# SBC-Accelerometer-v10.net
KiCad netlist of a schematic drawn in EAGLE
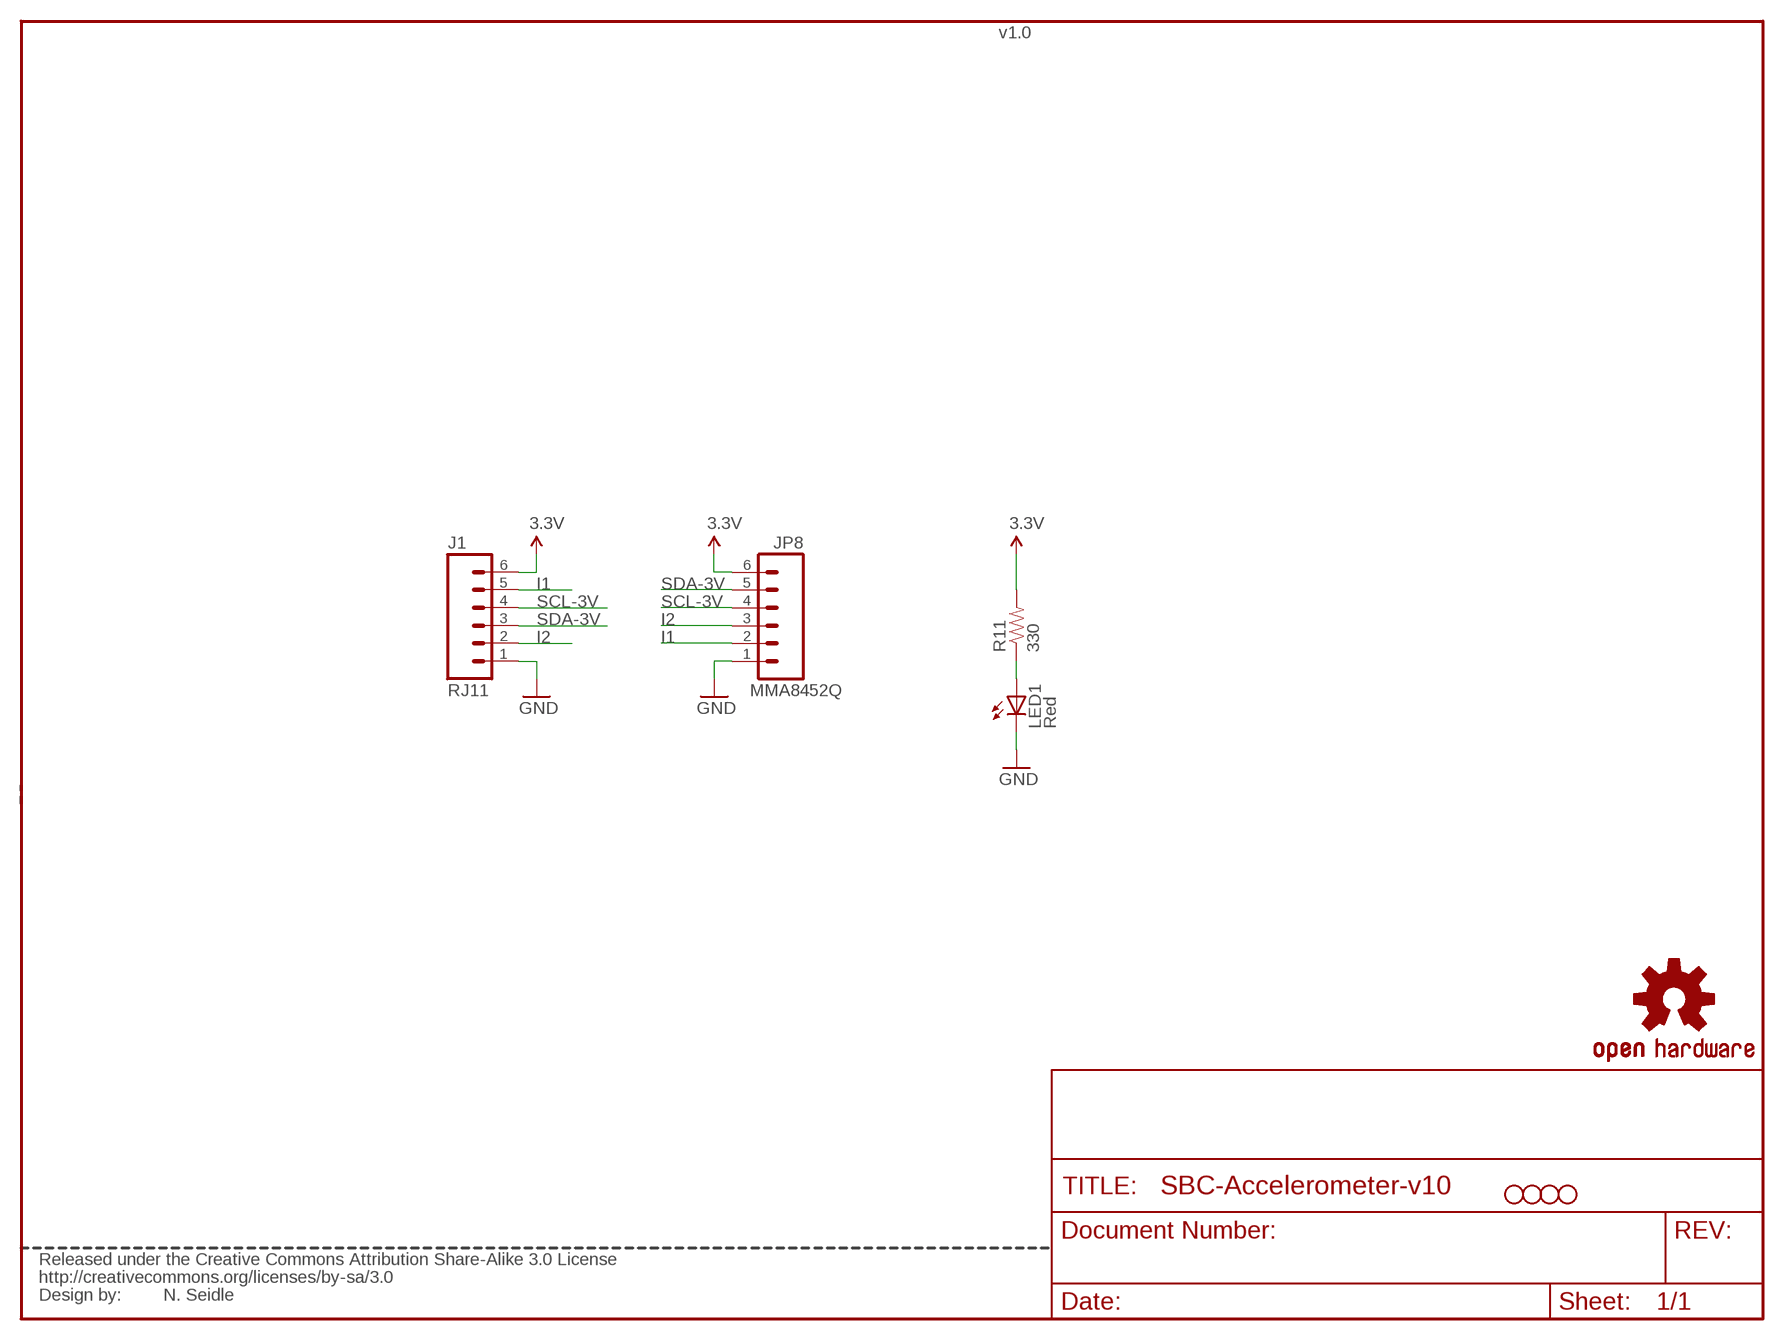
[diagram p0: schematic, sheet 1]

(export (version "E")
  (design (tool "Eeschema 10.0.6"))
  (components
    (comp (ref "J1")
      (value "RJ11")
      (footprint "eagle-import:RJ11-6")
      (libsource (lib "eagle-import") (part "RJ11-6PTH"))
    )
    (comp (ref "JP3")
      (value "STAND-OFF")
      (footprint "eagle-import:STAND-OFF")
      (libsource (lib "eagle-import") (part "STAND-OFF"))
    )
    (comp (ref "JP4")
      (value "STAND-OFF")
      (footprint "eagle-import:STAND-OFF")
      (libsource (lib "eagle-import") (part "STAND-OFF"))
    )
    (comp (ref "JP5")
      (value "STAND-OFF")
      (footprint "eagle-import:STAND-OFF")
      (libsource (lib "eagle-import") (part "STAND-OFF"))
    )
    (comp (ref "JP6")
      (value "STAND-OFF")
      (footprint "eagle-import:STAND-OFF")
      (libsource (lib "eagle-import") (part "STAND-OFF"))
    )
    (comp (ref "JP8")
      (value "MMA8452Q")
      (footprint "eagle-import:1X06")
      (libsource (lib "eagle-import") (part "M06SIP"))
    )
    (comp (ref "LED1")
      (value "Red")
      (footprint "eagle-import:LED3MM")
      (libsource (lib "eagle-import") (part "LED3MM"))
    )
    (comp (ref "R11")
      (value "330")
      (footprint "eagle-import:AXIAL-0.3")
      (libsource (lib "eagle-import") (part "RESISTORAXIAL-0.3"))
    )
    (comp (ref "U$3")
      (value "CREATIVE_COMMONS")
      (footprint "eagle-import:CREATIVE_COMMONS")
      (libsource (lib "eagle-import") (part "CREATIVE_COMMONS"))
    )
    (comp (ref "U$4")
      (value "OSHW-LOGOS")
      (footprint "eagle-import:OSHW-LOGO-S")
      (libsource (lib "eagle-import") (part "OSHW-LOGOS"))
    )
  )
  (nets
    (net (code "1") (name "/I1") (class "Default")
      (node (ref "J1") (pin "5") (pinfunction "5_5") (pintype "passive"))
      (node (ref "JP8") (pin "2") (pinfunction "2_2") (pintype "passive"))
    )
    (net (code "2") (name "/I2") (class "Default")
      (node (ref "J1") (pin "2") (pinfunction "2_2") (pintype "passive"))
      (node (ref "JP8") (pin "3") (pinfunction "3_3") (pintype "passive"))
    )
    (net (code "3") (name "/SCL-3V") (class "Default")
      (node (ref "J1") (pin "4") (pinfunction "4_4") (pintype "passive"))
      (node (ref "JP8") (pin "4") (pinfunction "4_4") (pintype "passive"))
    )
    (net (code "4") (name "/SDA-3V") (class "Default")
      (node (ref "J1") (pin "3") (pinfunction "3_3") (pintype "passive"))
      (node (ref "JP8") (pin "5") (pinfunction "5_5") (pintype "passive"))
    )
    (net (code "5") (name "3.3V") (class "Default")
      (node (ref "J1") (pin "6") (pinfunction "6_6") (pintype "passive"))
      (node (ref "JP8") (pin "6") (pinfunction "6_6") (pintype "passive"))
      (node (ref "R11") (pin "P$2") (pinfunction "2_P$2") (pintype "passive"))
    )
    (net (code "6") (name "GND") (class "Default")
      (node (ref "J1") (pin "1") (pinfunction "1_1") (pintype "passive"))
      (node (ref "JP8") (pin "1") (pinfunction "1_1") (pintype "passive"))
      (node (ref "LED1") (pin "K") (pinfunction "C_K") (pintype "passive"))
    )
    (net (code "7") (name "Net-(R11-1)") (class "Default")
      (node (ref "LED1") (pin "A") (pinfunction "A_A") (pintype "passive"))
      (node (ref "R11") (pin "P$1") (pinfunction "1_P$1") (pintype "passive"))
    )
  )
)
